# ctp.net
KiCad netlist of a schematic drawn in EAGLE
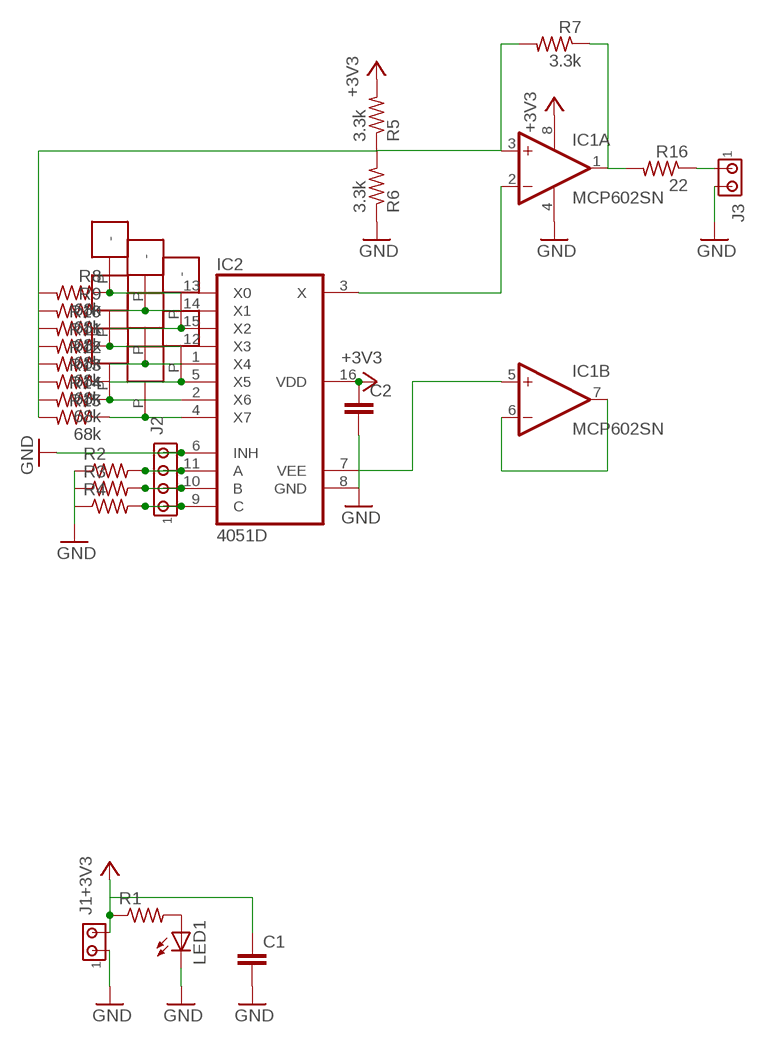
[diagram p0: schematic, sheet 1]

(export (version "E")
  (design (tool "Eeschema 10.0.6"))
  (components
    (comp (ref "C1")
      (value "C-EUC0805")
      (footprint "eagle-import:C0805")
      (libsource (lib "eagle-import") (part "C-EUC0805"))
    )
    (comp (ref "C2")
      (value "C-EUC0805")
      (footprint "eagle-import:C0805")
      (libsource (lib "eagle-import") (part "C-EUC0805"))
    )
    (comp (ref "IC1")
      (value "MCP602SN")
      (footprint "eagle-import:SO08")
      (libsource (lib "eagle-import") (part "MCP602SN"))
    )
    (comp (ref "IC2")
      (value "4051D")
      (footprint "eagle-import:SO16")
      (libsource (lib "eagle-import") (part "4051D"))
    )
    (comp (ref "J1")
      (value "MTA02-100")
      (footprint "eagle-import:10X02MTA")
      (libsource (lib "eagle-import") (part "MTA02-100"))
    )
    (comp (ref "J2")
      (value "MTA04-100")
      (footprint "eagle-import:10X04MTA")
      (libsource (lib "eagle-import") (part "MTA04-100"))
    )
    (comp (ref "J3")
      (value "MTA02-100")
      (footprint "eagle-import:10X02MTA")
      (libsource (lib "eagle-import") (part "MTA02-100"))
    )
    (comp (ref "LED1")
      (value "LEDCHIP-LED0805")
      (footprint "eagle-import:CHIP-LED0805")
      (libsource (lib "eagle-import") (part "LEDCHIP-LED0805"))
    )
    (comp (ref "R1")
      (value "R-US_M0805")
      (footprint "eagle-import:M0805")
      (libsource (lib "eagle-import") (part "R-US_M0805"))
    )
    (comp (ref "R2")
      (value "R-US_M0805")
      (footprint "eagle-import:M0805")
      (libsource (lib "eagle-import") (part "R-US_M0805"))
    )
    (comp (ref "R3")
      (value "R-US_M0805")
      (footprint "eagle-import:M0805")
      (libsource (lib "eagle-import") (part "R-US_M0805"))
    )
    (comp (ref "R4")
      (value "R-US_M0805")
      (footprint "eagle-import:M0805")
      (libsource (lib "eagle-import") (part "R-US_M0805"))
    )
    (comp (ref "R5")
      (value "3.3k")
      (footprint "eagle-import:M0805")
      (libsource (lib "eagle-import") (part "R-US_M0805"))
    )
    (comp (ref "R6")
      (value "3.3k")
      (footprint "eagle-import:M0805")
      (libsource (lib "eagle-import") (part "R-US_M0805"))
    )
    (comp (ref "R7")
      (value "3.3k")
      (footprint "eagle-import:M0805")
      (libsource (lib "eagle-import") (part "R-US_M0805"))
    )
    (comp (ref "R8")
      (value "68k")
      (footprint "eagle-import:M0805")
      (libsource (lib "eagle-import") (part "R-US_M0805"))
    )
    (comp (ref "R9")
      (value "68k")
      (footprint "eagle-import:M0805")
      (libsource (lib "eagle-import") (part "R-US_M0805"))
    )
    (comp (ref "R10")
      (value "68k")
      (footprint "eagle-import:M0805")
      (libsource (lib "eagle-import") (part "R-US_M0805"))
    )
    (comp (ref "R11")
      (value "68k")
      (footprint "eagle-import:M0805")
      (libsource (lib "eagle-import") (part "R-US_M0805"))
    )
    (comp (ref "R12")
      (value "68k")
      (footprint "eagle-import:M0805")
      (libsource (lib "eagle-import") (part "R-US_M0805"))
    )
    (comp (ref "R13")
      (value "68k")
      (footprint "eagle-import:M0805")
      (libsource (lib "eagle-import") (part "R-US_M0805"))
    )
    (comp (ref "R14")
      (value "68k")
      (footprint "eagle-import:M0805")
      (libsource (lib "eagle-import") (part "R-US_M0805"))
    )
    (comp (ref "R15")
      (value "68k")
      (footprint "eagle-import:M0805")
      (libsource (lib "eagle-import") (part "R-US_M0805"))
    )
    (comp (ref "R16")
      (value "22")
      (footprint "eagle-import:M0805")
      (libsource (lib "eagle-import") (part "R-US_M0805"))
    )
    (comp (ref "U$1")
      (value "BUTTON")
      (footprint "eagle-import:CTP1")
      (libsource (lib "eagle-import") (part "BUTTON"))
    )
    (comp (ref "U$2")
      (value "BUTTON")
      (footprint "eagle-import:CTP1")
      (libsource (lib "eagle-import") (part "BUTTON"))
    )
    (comp (ref "U$3")
      (value "BUTTON")
      (footprint "eagle-import:CTP1")
      (libsource (lib "eagle-import") (part "BUTTON"))
    )
    (comp (ref "U$4")
      (value "BUTTON")
      (footprint "eagle-import:CTP1")
      (libsource (lib "eagle-import") (part "BUTTON"))
    )
    (comp (ref "U$5")
      (value "BUTTON")
      (footprint "eagle-import:CTP1")
      (libsource (lib "eagle-import") (part "BUTTON"))
    )
    (comp (ref "U$6")
      (value "BUTTON")
      (footprint "eagle-import:CTP1")
      (libsource (lib "eagle-import") (part "BUTTON"))
    )
    (comp (ref "U$7")
      (value "BUTTON")
      (footprint "eagle-import:CTP1")
      (libsource (lib "eagle-import") (part "BUTTON"))
    )
    (comp (ref "U$8")
      (value "BUTTON")
      (footprint "eagle-import:CTP1")
      (libsource (lib "eagle-import") (part "BUTTON"))
    )
  )
  (nets
    (net (code "1") (name "+3V3") (class "Default")
      (node (ref "C1") (pin "1") (pinfunction "1_1") (pintype "passive"))
      (node (ref "C2") (pin "1") (pinfunction "1_1") (pintype "passive"))
      (node (ref "IC1") (pin "8") (pinfunction "V+_8") (pintype "power_in"))
      (node (ref "IC2") (pin "16") (pinfunction "VDD_16") (pintype "bidirectional"))
      (node (ref "J1") (pin "2") (pinfunction "2_2") (pintype "passive"))
      (node (ref "R1") (pin "1") (pinfunction "1_1") (pintype "passive"))
      (node (ref "R5") (pin "2") (pinfunction "2_2") (pintype "passive"))
    )
    (net (code "2") (name "GND") (class "Default")
      (node (ref "C1") (pin "2") (pinfunction "2_2") (pintype "passive"))
      (node (ref "C2") (pin "2") (pinfunction "2_2") (pintype "passive"))
      (node (ref "IC1") (pin "4") (pinfunction "V-_4") (pintype "power_in"))
      (node (ref "IC1") (pin "5") (pinfunction "+IN_5") (pintype "input"))
      (node (ref "IC2") (pin "6") (pinfunction "INH_6") (pintype "input"))
      (node (ref "IC2") (pin "7") (pinfunction "VEE_7") (pintype "bidirectional"))
      (node (ref "IC2") (pin "8") (pinfunction "GND_8") (pintype "bidirectional"))
      (node (ref "J1") (pin "1") (pinfunction "1_1") (pintype "passive"))
      (node (ref "J2") (pin "4") (pinfunction "4_4") (pintype "passive"))
      (node (ref "J3") (pin "2") (pinfunction "2_2") (pintype "passive"))
      (node (ref "LED1") (pin "C") (pinfunction "C_C") (pintype "passive"))
      (node (ref "R2") (pin "1") (pinfunction "1_1") (pintype "passive"))
      (node (ref "R3") (pin "1") (pinfunction "1_1") (pintype "passive"))
      (node (ref "R4") (pin "1") (pinfunction "1_1") (pintype "passive"))
      (node (ref "R6") (pin "1") (pinfunction "1_1") (pintype "passive"))
    )
    (net (code "3") (name "Net-(IC1A-+IN)") (class "Default")
      (node (ref "IC1") (pin "3") (pinfunction "+IN_3") (pintype "input"))
      (node (ref "R10") (pin "2") (pinfunction "2_2") (pintype "passive"))
      (node (ref "R11") (pin "2") (pinfunction "2_2") (pintype "passive"))
      (node (ref "R12") (pin "2") (pinfunction "2_2") (pintype "passive"))
      (node (ref "R13") (pin "2") (pinfunction "2_2") (pintype "passive"))
      (node (ref "R14") (pin "2") (pinfunction "2_2") (pintype "passive"))
      (node (ref "R15") (pin "2") (pinfunction "2_2") (pintype "passive"))
      (node (ref "R5") (pin "1") (pinfunction "1_1") (pintype "passive"))
      (node (ref "R6") (pin "2") (pinfunction "2_2") (pintype "passive"))
      (node (ref "R7") (pin "2") (pinfunction "2_2") (pintype "passive"))
      (node (ref "R8") (pin "2") (pinfunction "2_2") (pintype "passive"))
      (node (ref "R9") (pin "2") (pinfunction "2_2") (pintype "passive"))
    )
    (net (code "4") (name "Net-(IC1A--IN)") (class "Default")
      (node (ref "IC1") (pin "2") (pinfunction "-IN_2") (pintype "input"))
      (node (ref "IC2") (pin "3") (pinfunction "X_3") (pintype "bidirectional"))
    )
    (net (code "5") (name "Net-(IC1A-OUT)") (class "Default")
      (node (ref "IC1") (pin "1") (pinfunction "OUT_1") (pintype "output"))
      (node (ref "R16") (pin "2") (pinfunction "2_2") (pintype "passive"))
      (node (ref "R7") (pin "1") (pinfunction "1_1") (pintype "passive"))
    )
    (net (code "6") (name "Net-(IC1B--IN)") (class "Default")
      (node (ref "IC1") (pin "6") (pinfunction "-IN_6") (pintype "input"))
      (node (ref "IC1") (pin "7") (pinfunction "OUT_7") (pintype "output"))
    )
    (net (code "7") (name "Net-(IC2-A)") (class "Default")
      (node (ref "IC2") (pin "11") (pinfunction "A_11") (pintype "input"))
      (node (ref "J2") (pin "3") (pinfunction "3_3") (pintype "passive"))
      (node (ref "R2") (pin "2") (pinfunction "2_2") (pintype "passive"))
    )
    (net (code "8") (name "Net-(IC2-B)") (class "Default")
      (node (ref "IC2") (pin "10") (pinfunction "B_10") (pintype "input"))
      (node (ref "J2") (pin "2") (pinfunction "2_2") (pintype "passive"))
      (node (ref "R3") (pin "2") (pinfunction "2_2") (pintype "passive"))
    )
    (net (code "9") (name "Net-(IC2-C)") (class "Default")
      (node (ref "IC2") (pin "9") (pinfunction "C_9") (pintype "input"))
      (node (ref "J2") (pin "1") (pinfunction "1_1") (pintype "passive"))
      (node (ref "R4") (pin "2") (pinfunction "2_2") (pintype "passive"))
    )
    (net (code "10") (name "Net-(IC2-X0)") (class "Default")
      (node (ref "IC2") (pin "13") (pinfunction "X0_13") (pintype "bidirectional"))
      (node (ref "R8") (pin "1") (pinfunction "1_1") (pintype "passive"))
      (node (ref "U$1") (pin "P") (pinfunction "-_P") (pintype "input"))
    )
    (net (code "11") (name "Net-(IC2-X1)") (class "Default")
      (node (ref "IC2") (pin "14") (pinfunction "X1_14") (pintype "bidirectional"))
      (node (ref "R9") (pin "1") (pinfunction "1_1") (pintype "passive"))
      (node (ref "U$2") (pin "P") (pinfunction "-_P") (pintype "input"))
    )
    (net (code "12") (name "Net-(IC2-X2)") (class "Default")
      (node (ref "IC2") (pin "15") (pinfunction "X2_15") (pintype "bidirectional"))
      (node (ref "R10") (pin "1") (pinfunction "1_1") (pintype "passive"))
      (node (ref "U$3") (pin "P") (pinfunction "-_P") (pintype "input"))
    )
    (net (code "13") (name "Net-(IC2-X3)") (class "Default")
      (node (ref "IC2") (pin "12") (pinfunction "X3_12") (pintype "bidirectional"))
      (node (ref "R11") (pin "1") (pinfunction "1_1") (pintype "passive"))
      (node (ref "U$4") (pin "P") (pinfunction "-_P") (pintype "input"))
    )
    (net (code "14") (name "Net-(IC2-X4)") (class "Default")
      (node (ref "IC2") (pin "1") (pinfunction "X4_1") (pintype "bidirectional"))
      (node (ref "R12") (pin "1") (pinfunction "1_1") (pintype "passive"))
      (node (ref "U$5") (pin "P") (pinfunction "-_P") (pintype "input"))
    )
    (net (code "15") (name "Net-(IC2-X5)") (class "Default")
      (node (ref "IC2") (pin "5") (pinfunction "X5_5") (pintype "bidirectional"))
      (node (ref "R13") (pin "1") (pinfunction "1_1") (pintype "passive"))
      (node (ref "U$6") (pin "P") (pinfunction "-_P") (pintype "input"))
    )
    (net (code "16") (name "Net-(IC2-X6)") (class "Default")
      (node (ref "IC2") (pin "2") (pinfunction "X6_2") (pintype "bidirectional"))
      (node (ref "R14") (pin "1") (pinfunction "1_1") (pintype "passive"))
      (node (ref "U$7") (pin "P") (pinfunction "-_P") (pintype "input"))
    )
    (net (code "17") (name "Net-(IC2-X7)") (class "Default")
      (node (ref "IC2") (pin "4") (pinfunction "X7_4") (pintype "bidirectional"))
      (node (ref "R15") (pin "1") (pinfunction "1_1") (pintype "passive"))
      (node (ref "U$8") (pin "P") (pinfunction "-_P") (pintype "input"))
    )
    (net (code "18") (name "Net-(J3-Pad1)") (class "Default")
      (node (ref "J3") (pin "1") (pinfunction "1_1") (pintype "passive"))
      (node (ref "R16") (pin "1") (pinfunction "1_1") (pintype "passive"))
    )
    (net (code "19") (name "Net-(LED1-PadA)") (class "Default")
      (node (ref "LED1") (pin "A") (pinfunction "A_A") (pintype "passive"))
      (node (ref "R1") (pin "2") (pinfunction "2_2") (pintype "passive"))
    )
  )
)
